# CAN.net
KiCad netlist of a schematic drawn in Altium Designer
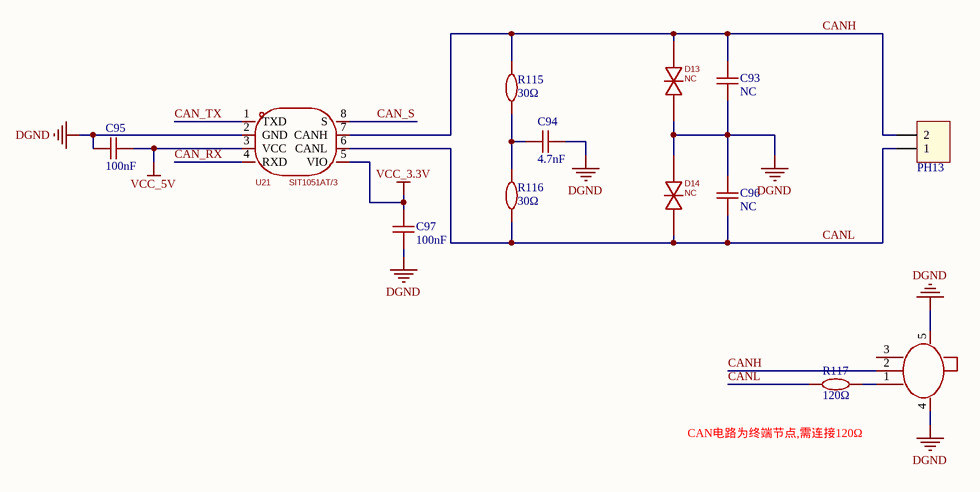
[diagram p0: CAN.SchDoc]

(export (version "E")
  (design (tool "Eeschema 10.0.6"))
  (components
    (comp (ref "C93")
      (value "NC")
      (footprint "C0603")
      (libsource (lib "XG_DW_POCT_2K10LED_3") (part "NC,C0603"))
    )
    (comp (ref "C94")
      (value "4.7nF")
      (footprint "C0603")
      (description "贴片电容,X7R")
      (libsource (lib "XG_DW_POCT_2K10LED_3") (part "4.7nF/50V,C0603"))
    )
    (comp (ref "C95")
      (value "100nF")
      (footprint "C0603")
      (description "贴片电容,X7R")
      (libsource (lib "XG_DW_POCT_2K10LED_3") (part "100nF/50V,C0603"))
    )
    (comp (ref "C96")
      (value "NC")
      (footprint "C0603")
      (libsource (lib "XG_DW_POCT_2K10LED_3") (part "NC,C0603"))
    )
    (comp (ref "C97")
      (value "100nF")
      (footprint "C0603")
      (description "贴片电容,X7R")
      (libsource (lib "XG_DW_POCT_2K10LED_3") (part "100nF/50V,C0603"))
    )
    (comp (ref "D13")
      (value "NC")
      (footprint "SOD-523_L1.2-W0.8-LS1.6-BI")
      (description "RSB6.8STE61")
      (libsource (lib "XG_DW_POCT_2K10LED_3") (part "NC,RSB6.8STE61"))
    )
    (comp (ref "D14")
      (value "NC")
      (footprint "SOD-523_L1.2-W0.8-LS1.6-BI")
      (description "RSB6.8STE61")
      (libsource (lib "XG_DW_POCT_2K10LED_3") (part "NC,RSB6.8STE61"))
    )
    (comp (ref "PH13")
      (value "PH2.0-2P")
      (footprint "PH2.0-2P 弯针")
      (libsource (lib "XG_DW_POCT_2K10LED_3") (part "PH2.0-2P"))
    )
    (comp (ref "R115")
      (value "30Ω")
      (footprint "R0603")
      (description "贴片电阻")
      (libsource (lib "XG_DW_POCT_2K10LED_3") (part "30Ω,R0603"))
    )
    (comp (ref "R116")
      (value "30Ω")
      (footprint "R0603")
      (description "贴片电阻")
      (libsource (lib "XG_DW_POCT_2K10LED_3") (part "30Ω,R0603"))
    )
    (comp (ref "R117")
      (value "120Ω")
      (footprint "R0603")
      (description "贴片电阻")
      (libsource (lib "XG_DW_POCT_2K10LED_3") (part "120Ω,R0603"))
    )
    (comp (ref "SW1")
      (value "MINI MSK12CO2")
      (footprint "SW-SMD_MSK12CO2")
      (fields (field (name "MANUFACTURER") "SHOU HAN(首韩)"))
      (libsource (lib "altium-import") (part "root_1_MINI MSK12CO2_"))
    )
    (comp (ref "U21")
      (value "SIT1051AT/3")
      (footprint "SOP-8_L4.9-W3.9-P1.27-LS6.0-BL")
      (fields (field (name "MANUFACTURER") "SIT(芯力特)"))
      (libsource (lib "XG_DW_POCT_2K10LED_3") (part "SIT1051AT/3"))
    )
  )
  (nets
    (net (code "1") (name "/CANH") (class "Default")
      (node (ref "C93") (pin "2") (pinfunction "2_2") (pintype "passive"))
      (node (ref "D13") (pin "2") (pinfunction "A_2") (pintype "passive"))
      (node (ref "PH13") (pin "2") (pinfunction "2_2") (pintype "passive"))
      (node (ref "R115") (pin "2") (pinfunction "2_2") (pintype "passive"))
      (node (ref "SW1") (pin "2") (pinfunction "2_2") (pintype "passive"))
      (node (ref "U21") (pin "7") (pinfunction "CANH_7") (pintype "passive"))
    )
    (net (code "2") (name "/CANL") (class "Default")
      (node (ref "C96") (pin "1") (pinfunction "1_1") (pintype "passive"))
      (node (ref "D14") (pin "1") (pinfunction "C_1") (pintype "passive"))
      (node (ref "PH13") (pin "1") (pinfunction "1_1") (pintype "passive"))
      (node (ref "R116") (pin "1") (pinfunction "1_1") (pintype "passive"))
      (node (ref "R117") (pin "2") (pinfunction "2_2") (pintype "passive"))
      (node (ref "U21") (pin "6") (pinfunction "CANL_6") (pintype "passive"))
    )
    (net (code "3") (name "/CAN_RX") (class "Default")
      (node (ref "U21") (pin "4") (pinfunction "RXD_4") (pintype "passive"))
    )
    (net (code "4") (name "/CAN_S") (class "Default")
      (node (ref "U21") (pin "8") (pinfunction "S_8") (pintype "passive"))
    )
    (net (code "5") (name "/CAN_TX") (class "Default")
      (node (ref "U21") (pin "1") (pinfunction "TXD_1") (pintype "passive"))
    )
    (net (code "6") (name "DGND") (class "Default")
      (node (ref "C93") (pin "1") (pinfunction "1_1") (pintype "passive"))
      (node (ref "C94") (pin "2") (pinfunction "2_2") (pintype "passive"))
      (node (ref "C95") (pin "2") (pinfunction "2_2") (pintype "passive"))
      (node (ref "C96") (pin "2") (pinfunction "2_2") (pintype "passive"))
      (node (ref "C97") (pin "2") (pinfunction "2_2") (pintype "passive"))
      (node (ref "D13") (pin "1") (pinfunction "C_1") (pintype "passive"))
      (node (ref "D14") (pin "2") (pinfunction "A_2") (pintype "passive"))
      (node (ref "SW1") (pin "4") (pinfunction "4_4") (pintype "passive"))
      (node (ref "SW1") (pin "5") (pinfunction "5_5") (pintype "passive"))
      (node (ref "U21") (pin "2") (pinfunction "GND_2") (pintype "passive"))
    )
    (net (code "7") (name "Net-(C94-Pad1)") (class "Default")
      (node (ref "C94") (pin "1") (pinfunction "1_1") (pintype "passive"))
      (node (ref "R115") (pin "1") (pinfunction "1_1") (pintype "passive"))
      (node (ref "R116") (pin "2") (pinfunction "2_2") (pintype "passive"))
    )
    (net (code "8") (name "Net-(R117-Pad1)") (class "Default")
      (node (ref "R117") (pin "1") (pinfunction "1_1") (pintype "passive"))
      (node (ref "SW1") (pin "1") (pinfunction "1_1") (pintype "passive"))
    )
    (net (code "9") (name "VCC_3.3V") (class "Default")
      (node (ref "C97") (pin "1") (pinfunction "1_1") (pintype "passive"))
      (node (ref "U21") (pin "5") (pinfunction "VIO_5") (pintype "passive"))
    )
    (net (code "10") (name "VCC_5V") (class "Default")
      (node (ref "C95") (pin "1") (pinfunction "1_1") (pintype "passive"))
      (node (ref "U21") (pin "3") (pinfunction "VCC_3") (pintype "passive"))
    )
    (net (code "11") (name "unconnected-(SW1-Pad3)") (class "Default")
      (node (ref "SW1") (pin "3") (pinfunction "3_3") (pintype "passive"))
    )
  )
)
